# Temperature_Units.net
KiCad netlist of a schematic drawn in Altium Designer
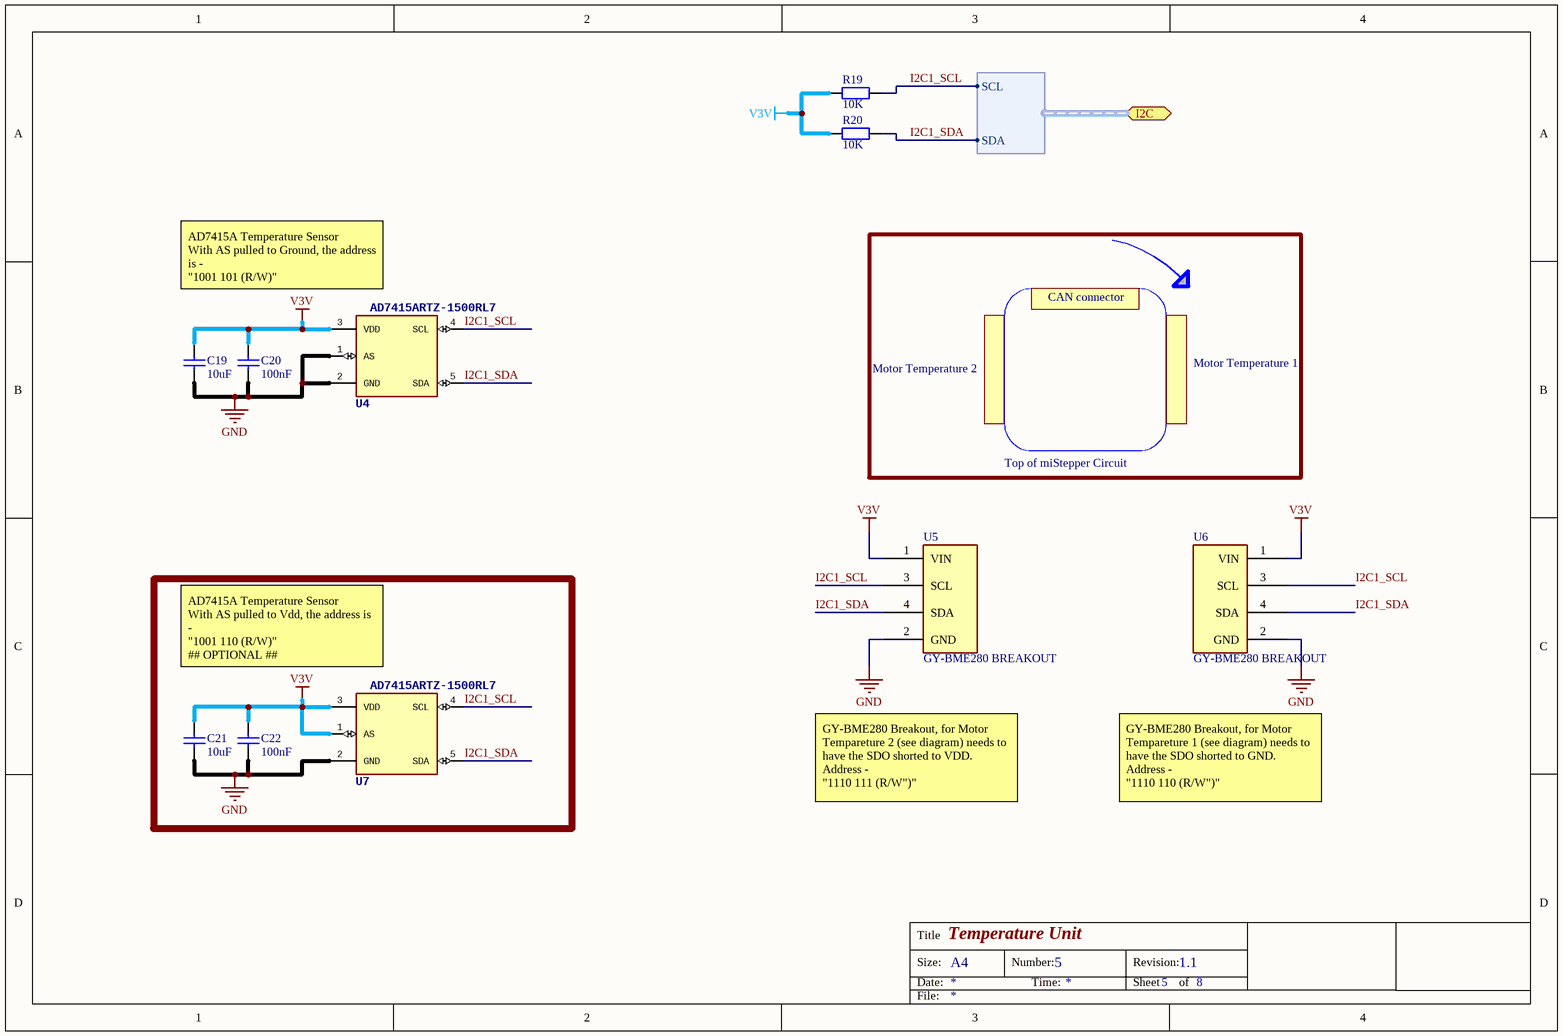
[diagram p0: Temperature_Units.SchDoc]

(export (version "E")
  (design (tool "Eeschema 10.0.6"))
  (components
    (comp (ref "C19")
      (value "10uF")
      (footprint "CAPC1608X06N (0603)")
      (description "Capacitor (Semiconductor SIM Model)")
      (fields (field (name "Comment") "Cap Semi") (field (name "PUBLISHER") "Altium Limited"))
      (libsource (lib "miStepper_SchematicLib") (part "Cap Semi"))
    )
    (comp (ref "C20")
      (value "100nF")
      (footprint "CAPC1608X06N (0603)")
      (description "Capacitor (Semiconductor SIM Model)")
      (fields (field (name "Comment") "Cap Semi") (field (name "PUBLISHER") "Altium Limited"))
      (libsource (lib "miStepper_SchematicLib") (part "Cap Semi"))
    )
    (comp (ref "C21")
      (value "10uF")
      (footprint "CAPC1608X06N (0603)")
      (description "Capacitor (Semiconductor SIM Model)")
      (fields (field (name "Comment") "Cap Semi") (field (name "PUBLISHER") "Altium Limited"))
      (libsource (lib "miStepper_SchematicLib") (part "Cap Semi"))
    )
    (comp (ref "C22")
      (value "100nF")
      (footprint "CAPC1608X06N (0603)")
      (description "Capacitor (Semiconductor SIM Model)")
      (fields (field (name "Comment") "Cap Semi") (field (name "PUBLISHER") "Altium Limited"))
      (libsource (lib "miStepper_SchematicLib") (part "Cap Semi"))
    )
    (comp (ref "R19")
      (value "10K")
      (footprint "RESC1608X06N (0603)")
      (description "Resistor")
      (fields (field (name "Comment") "Res") (field (name "PUBLISHER") "Altium Limited"))
      (libsource (lib "miStepper_SchematicLib") (part "Res"))
    )
    (comp (ref "R20")
      (value "10K")
      (footprint "RESC1608X06N (0603)")
      (description "Resistor")
      (fields (field (name "Comment") "Res") (field (name "PUBLISHER") "Altium Limited"))
      (libsource (lib "miStepper_SchematicLib") (part "Res"))
    )
    (comp (ref "U4")
      (value "AD7415ARTZ-1500RL7")
      (footprint "SOT95P280X145-5N")
      (description "I2C Temperature Sensor")
      (fields
        (field (name "MOUSER_PART_NUMBER") "584-AD7415ARTZ1500R7")
        (field (name "RS_PART_NUMBER") "6977035P")
      )
      (libsource (lib "miStepper_SchematicLib") (part "AD7415ARTZ-1500RL7"))
    )
    (comp (ref "U5")
      (value "GY-BME280 BREAKOUT")
      (footprint "GY-BME280 BREAKOUT")
      (libsource (lib "") (part "GY-BME280 BREAKOUT_1"))
    )
    (comp (ref "U6")
      (value "GY-BME280 BREAKOUT")
      (footprint "GY-BME280 BREAKOUT")
      (libsource (lib "miStepper_SchematicLib") (part "GY-BME280 BREAKOUT"))
    )
    (comp (ref "U7")
      (value "AD7415ARTZ-1500RL7")
      (footprint "SOT95P280X145-5N")
      (description "I2C Temperature Sensor")
      (fields
        (field (name "MOUSER_PART_NUMBER") "584-AD7415ARTZ1500R7")
        (field (name "RS_PART_NUMBER") "6977035P")
      )
      (libsource (lib "miStepper_SchematicLib") (part "AD7415ARTZ-1500RL7"))
    )
  )
  (nets
    (net (code "2") (name "/I2C1_SCL") (class "Default")
      (node (ref "R19") (pin "1") (pinfunction "1_1") (pintype "passive"))
      (node (ref "U4") (pin "4") (pinfunction "SCL_4") (pintype "bidirectional"))
      (node (ref "U5") (pin "3") (pinfunction "SCL_3") (pintype "passive"))
      (node (ref "U6") (pin "3") (pinfunction "SCL_3") (pintype "passive"))
      (node (ref "U7") (pin "4") (pinfunction "SCL_4") (pintype "bidirectional"))
    )
    (net (code "3") (name "/I2C1_SDA") (class "Default")
      (node (ref "R20") (pin "1") (pinfunction "1_1") (pintype "passive"))
      (node (ref "U4") (pin "5") (pinfunction "SDA_5") (pintype "bidirectional"))
      (node (ref "U5") (pin "4") (pinfunction "SDA_4") (pintype "passive"))
      (node (ref "U6") (pin "4") (pinfunction "SDA_4") (pintype "passive"))
      (node (ref "U7") (pin "5") (pinfunction "SDA_5") (pintype "bidirectional"))
    )
    (net (code "5") (name "GND") (class "Default")
      (node (ref "C19") (pin "1") (pinfunction "1_1") (pintype "passive"))
      (node (ref "C20") (pin "1") (pinfunction "1_1") (pintype "passive"))
      (node (ref "C21") (pin "1") (pinfunction "1_1") (pintype "passive"))
      (node (ref "C22") (pin "1") (pinfunction "1_1") (pintype "passive"))
      (node (ref "U4") (pin "1") (pinfunction "AS_1") (pintype "bidirectional"))
      (node (ref "U4") (pin "2") (pinfunction "GND_2") (pintype "power_in"))
      (node (ref "U5") (pin "2") (pinfunction "GND_2") (pintype "passive"))
      (node (ref "U6") (pin "2") (pinfunction "GND_2") (pintype "passive"))
      (node (ref "U7") (pin "2") (pinfunction "GND_2") (pintype "power_in"))
    )
    (net (code "6") (name "V3V") (class "Default")
      (node (ref "C19") (pin "2") (pinfunction "2_2") (pintype "passive"))
      (node (ref "C20") (pin "2") (pinfunction "2_2") (pintype "passive"))
      (node (ref "C21") (pin "2") (pinfunction "2_2") (pintype "passive"))
      (node (ref "C22") (pin "2") (pinfunction "2_2") (pintype "passive"))
      (node (ref "R19") (pin "2") (pinfunction "2_2") (pintype "passive"))
      (node (ref "R20") (pin "2") (pinfunction "2_2") (pintype "passive"))
      (node (ref "U4") (pin "3") (pinfunction "VDD_3") (pintype "power_in"))
      (node (ref "U5") (pin "1") (pinfunction "VIN_1") (pintype "passive"))
      (node (ref "U6") (pin "1") (pinfunction "VIN_1") (pintype "passive"))
      (node (ref "U7") (pin "1") (pinfunction "AS_1") (pintype "bidirectional"))
      (node (ref "U7") (pin "3") (pinfunction "VDD_3") (pintype "power_in"))
    )
  )
)
